# Light_Sensor.net
KiCad netlist of a schematic drawn in Altium Designer
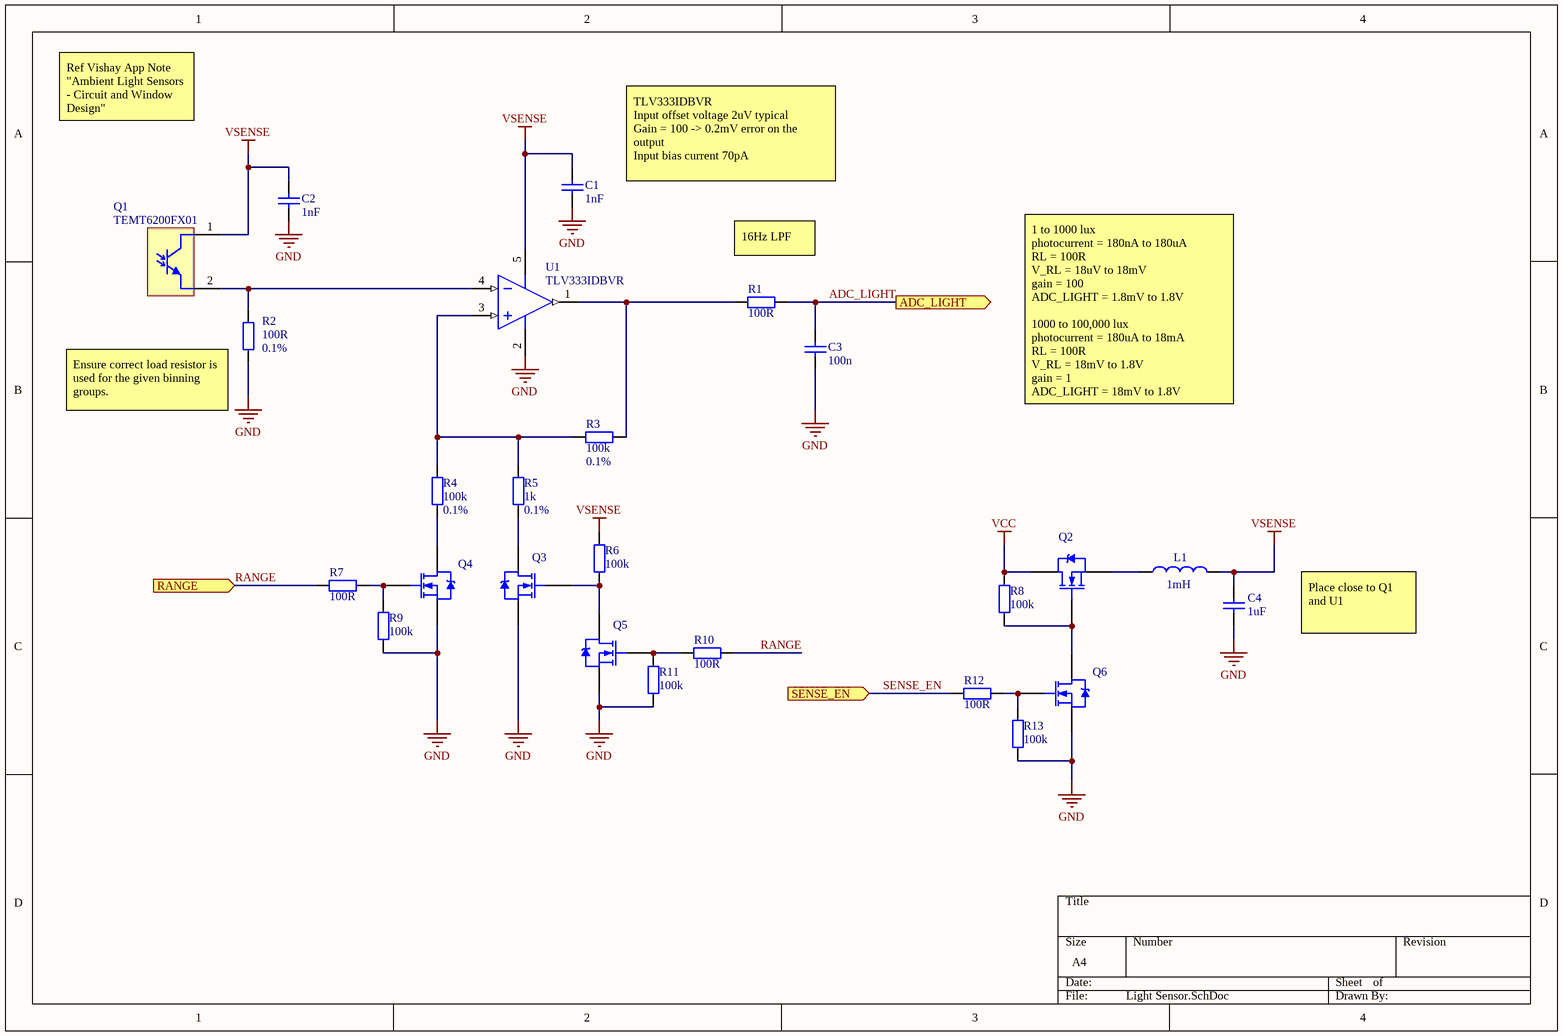
[diagram p0: Light Sensor.SchDoc]

(export (version "E")
  (design (tool "Eeschema 10.0.6"))
  (components
    (comp (ref "C1")
      (value "1nF")
      (footprint "C0603")
      (description "CAP")
      (fields
        (field (name "MANUFACTURER") "Yageo")
        (field (name "MANUFACTURER PART NUMBER") "CC0603KRX7R9BB102")
      )
      (libsource (lib "Light Sensor Node") (part "CAP"))
    )
    (comp (ref "C2")
      (value "1nF")
      (footprint "C0603")
      (description "CAP")
      (fields
        (field (name "MANUFACTURER") "Yageo")
        (field (name "MANUFACTURER PART NUMBER") "CC0603KRX7R9BB102")
      )
      (libsource (lib "Light Sensor Node") (part "CAP"))
    )
    (comp (ref "C3")
      (value "100n")
      (footprint "C0603")
      (description "CAP")
      (fields
        (field (name "MANUFACTURER") "Yageo")
        (field (name "MANUFACTURER PART NUMBER") "CC0603ZRY5V9BB104")
      )
      (libsource (lib "Light Sensor Node") (part "CAP"))
    )
    (comp (ref "C4")
      (value "~")
      (footprint "C0603")
      (description "CAP")
      (fields
        (field (name "MANUFACTURER") "Yageo")
        (field (name "MANUFACTURER PART NUMBER") "CC0603KRX7R9BB105")
        (field (name "CAPACITANCE") "1uF")
      )
      (libsource (lib "Light Sensor Node") (part "CAP"))
    )
    (comp (ref "L1")
      (value "IND")
      (footprint "TAIYOYUDEN_CB2518T102K")
      (fields
        (field (name "MANUFACTURER") "Taiyo Yuden")
        (field (name "MANUFACTURER PART NUMBER") "CB2518T102K")
        (field (name "INDUCTANCE") "1mH")
      )
      (libsource (lib "Light Sensor Node") (part "IND"))
    )
    (comp (ref "Q1")
      (value "TEMT6200FX01")
      (fields (field (name "MANUFACTURER") "Vishay"))
      (libsource (lib "Light Sensor Node") (part "VISHAY_TEMT6200FX01"))
    )
    (comp (ref "Q2")
      (value "2N7002ET1G")
      (footprint "ON_2N7002E")
      (fields (field (name "MANUFACTURER") "ON Semiconductor"))
      (libsource (lib "Light Sensor Node") (part "N-channel MOSFET"))
    )
    (comp (ref "Q3")
      (value "2N7002ET1G")
      (footprint "ON_2N7002E")
      (fields (field (name "MANUFACTURER") "ON Semiconductor"))
      (libsource (lib "Light Sensor Node") (part "N-channel MOSFET"))
    )
    (comp (ref "Q4")
      (value "2N7002ET1G")
      (footprint "ON_2N7002E")
      (fields (field (name "MANUFACTURER") "ON Semiconductor"))
      (libsource (lib "Light Sensor Node") (part "N-channel MOSFET"))
    )
    (comp (ref "Q5")
      (value "2N7002ET1G")
      (footprint "ON_2N7002E")
      (fields (field (name "MANUFACTURER") "ON Semiconductor"))
      (libsource (lib "Light Sensor Node") (part "N-channel MOSFET"))
    )
    (comp (ref "Q6")
      (value "2N7002ET1G")
      (footprint "ON_2N7002E")
      (fields (field (name "MANUFACTURER") "ON Semiconductor"))
      (libsource (lib "Light Sensor Node") (part "N-channel MOSFET"))
    )
    (comp (ref "R1")
      (value "100R")
      (footprint "R0603")
      (description "RES")
      (fields (field (name "TOLERANCE") "1%") (field (name "MANUFACTURER") "Yageo"))
      (libsource (lib "Light Sensor Node") (part "RES"))
    )
    (comp (ref "R2")
      (value "100R")
      (footprint "R0603")
      (description "RES")
      (fields
        (field (name "TOLERANCE") "0.1%")
        (field (name "MANUFACTURER") "Yageo")
        (field (name "MANUFACTURER PART NUMBER") "RT0603BRD07100RL")
      )
      (libsource (lib "") (part "RES_2"))
    )
    (comp (ref "R3")
      (value "100k")
      (footprint "R0603")
      (description "RES")
      (fields
        (field (name "TOLERANCE") "0.1%")
        (field (name "MANUFACTURER") "Yageo")
        (field (name "MANUFACTURER PART NUMBER") "RT0603BRD07100KL")
      )
      (libsource (lib "Light Sensor Node") (part "RES"))
    )
    (comp (ref "R4")
      (value "100k")
      (footprint "R0603")
      (description "RES")
      (fields
        (field (name "TOLERANCE") "0.1%")
        (field (name "MANUFACTURER") "Yageo")
        (field (name "MANUFACTURER PART NUMBER") "RT0603BRD07100KL")
      )
      (libsource (lib "") (part "RES_2"))
    )
    (comp (ref "R5")
      (value "1k")
      (footprint "R0603")
      (description "RES")
      (fields
        (field (name "TOLERANCE") "0.1%")
        (field (name "MANUFACTURER") "Yageo")
        (field (name "MANUFACTURER PART NUMBER") "RT0603BRD071KL")
      )
      (libsource (lib "") (part "RES_1"))
    )
    (comp (ref "R6")
      (value "100k")
      (footprint "R0603")
      (description "RES")
      (fields (field (name "TOLERANCE") "1%") (field (name "MANUFACTURER") "Yageo"))
      (libsource (lib "") (part "RES_1"))
    )
    (comp (ref "R7")
      (value "100R")
      (footprint "R0603")
      (description "RES")
      (fields (field (name "TOLERANCE") "1%") (field (name "MANUFACTURER") "Yageo"))
      (libsource (lib "Light Sensor Node") (part "RES"))
    )
    (comp (ref "R8")
      (value "100k")
      (footprint "R0603")
      (description "RES")
      (fields (field (name "TOLERANCE") "1%") (field (name "MANUFACTURER") "Yageo"))
      (libsource (lib "") (part "RES_1"))
    )
    (comp (ref "R9")
      (value "100k")
      (footprint "R0603")
      (description "RES")
      (fields (field (name "TOLERANCE") "1%") (field (name "MANUFACTURER") "Yageo"))
      (libsource (lib "") (part "RES_1"))
    )
    (comp (ref "R10")
      (value "100R")
      (footprint "R0603")
      (description "RES")
      (fields (field (name "TOLERANCE") "1%") (field (name "MANUFACTURER") "Yageo"))
      (libsource (lib "Light Sensor Node") (part "RES"))
    )
    (comp (ref "R11")
      (value "100k")
      (footprint "R0603")
      (description "RES")
      (fields (field (name "TOLERANCE") "1%") (field (name "MANUFACTURER") "Yageo"))
      (libsource (lib "") (part "RES_1"))
    )
    (comp (ref "R12")
      (value "100R")
      (footprint "R0603")
      (description "RES")
      (fields (field (name "TOLERANCE") "1%") (field (name "MANUFACTURER") "Yageo"))
      (libsource (lib "Light Sensor Node") (part "RES"))
    )
    (comp (ref "R13")
      (value "100k")
      (footprint "R0603")
      (description "RES")
      (fields (field (name "TOLERANCE") "1%") (field (name "MANUFACTURER") "Yageo"))
      (libsource (lib "") (part "RES_1"))
    )
    (comp (ref "U1")
      (value "TLV333IDBVR")
      (footprint "TI_TLV333IDBVR")
      (fields (field (name "MANUFACTURER") "Texas Instruments"))
      (libsource (lib "Light Sensor Node") (part "OPAMP"))
    )
  )
  (nets
    (net (code "1") (name "/ADC_LIGHT") (class "Default")
      (node (ref "C3") (pin "2") (pinfunction "2_2") (pintype "passive"))
      (node (ref "R1") (pin "2") (pinfunction "2_2") (pintype "passive"))
    )
    (net (code "2") (name "/RANGE") (class "Default")
      (node (ref "R10") (pin "2") (pinfunction "2_2") (pintype "passive"))
      (node (ref "R7") (pin "1") (pinfunction "1_1") (pintype "passive"))
    )
    (net (code "3") (name "/SENSE_EN") (class "Default")
      (node (ref "R12") (pin "1") (pinfunction "1_1") (pintype "passive"))
    )
    (net (code "4") (name "GND") (class "Default")
      (node (ref "C1") (pin "2") (pinfunction "2_2") (pintype "passive"))
      (node (ref "C2") (pin "2") (pinfunction "2_2") (pintype "passive"))
      (node (ref "C3") (pin "1") (pinfunction "1_1") (pintype "passive"))
      (node (ref "C4") (pin "1") (pinfunction "1_1") (pintype "passive"))
      (node (ref "Q3") (pin "2") (pinfunction "S_2") (pintype "passive"))
      (node (ref "Q4") (pin "2") (pinfunction "S_2") (pintype "passive"))
      (node (ref "Q5") (pin "2") (pinfunction "S_2") (pintype "passive"))
      (node (ref "Q6") (pin "2") (pinfunction "S_2") (pintype "passive"))
      (node (ref "R11") (pin "2") (pinfunction "2_2") (pintype "passive"))
      (node (ref "R13") (pin "2") (pinfunction "2_2") (pintype "passive"))
      (node (ref "R2") (pin "1") (pinfunction "1_1") (pintype "passive"))
      (node (ref "R9") (pin "2") (pinfunction "2_2") (pintype "passive"))
      (node (ref "U1") (pin "2") (pinfunction "V-_2") (pintype "power_in"))
    )
    (net (code "5") (name "Net-(Q1-E)") (class "Default")
      (node (ref "Q1") (pin "2") (pinfunction "E_2") (pintype "passive"))
      (node (ref "R2") (pin "2") (pinfunction "2_2") (pintype "passive"))
      (node (ref "U1") (pin "4") (pinfunction "IN_A-_4") (pintype "input"))
    )
    (net (code "6") (name "Net-(Q2-G)") (class "Default")
      (node (ref "Q2") (pin "1") (pinfunction "G_1") (pintype "passive"))
      (node (ref "Q6") (pin "3") (pinfunction "D_3") (pintype "passive"))
      (node (ref "R8") (pin "2") (pinfunction "2_2") (pintype "passive"))
    )
    (net (code "7") (name "Net-(Q2-S)") (class "Default")
      (node (ref "L1") (pin "2") (pinfunction "2_2") (pintype "passive"))
      (node (ref "Q2") (pin "2") (pinfunction "S_2") (pintype "passive"))
    )
    (net (code "8") (name "Net-(Q3-D)") (class "Default")
      (node (ref "Q3") (pin "3") (pinfunction "D_3") (pintype "passive"))
      (node (ref "R5") (pin "2") (pinfunction "2_2") (pintype "passive"))
    )
    (net (code "9") (name "Net-(Q3-G)") (class "Default")
      (node (ref "Q3") (pin "1") (pinfunction "G_1") (pintype "passive"))
      (node (ref "Q5") (pin "3") (pinfunction "D_3") (pintype "passive"))
      (node (ref "R6") (pin "2") (pinfunction "2_2") (pintype "passive"))
    )
    (net (code "10") (name "Net-(Q4-D)") (class "Default")
      (node (ref "Q4") (pin "3") (pinfunction "D_3") (pintype "passive"))
      (node (ref "R4") (pin "1") (pinfunction "1_1") (pintype "passive"))
    )
    (net (code "11") (name "Net-(Q4-G)") (class "Default")
      (node (ref "Q4") (pin "1") (pinfunction "G_1") (pintype "passive"))
      (node (ref "R7") (pin "2") (pinfunction "2_2") (pintype "passive"))
      (node (ref "R9") (pin "1") (pinfunction "1_1") (pintype "passive"))
    )
    (net (code "12") (name "Net-(Q5-G)") (class "Default")
      (node (ref "Q5") (pin "1") (pinfunction "G_1") (pintype "passive"))
      (node (ref "R10") (pin "1") (pinfunction "1_1") (pintype "passive"))
      (node (ref "R11") (pin "1") (pinfunction "1_1") (pintype "passive"))
    )
    (net (code "13") (name "Net-(Q6-G)") (class "Default")
      (node (ref "Q6") (pin "1") (pinfunction "G_1") (pintype "passive"))
      (node (ref "R12") (pin "2") (pinfunction "2_2") (pintype "passive"))
      (node (ref "R13") (pin "1") (pinfunction "1_1") (pintype "passive"))
    )
    (net (code "14") (name "Net-(U1-IN_A+)") (class "Default")
      (node (ref "R3") (pin "1") (pinfunction "1_1") (pintype "passive"))
      (node (ref "R4") (pin "2") (pinfunction "2_2") (pintype "passive"))
      (node (ref "R5") (pin "1") (pinfunction "1_1") (pintype "passive"))
      (node (ref "U1") (pin "3") (pinfunction "IN_A+_3") (pintype "input"))
    )
    (net (code "15") (name "Net-(U1-OUT_A)") (class "Default")
      (node (ref "R1") (pin "1") (pinfunction "1_1") (pintype "passive"))
      (node (ref "R3") (pin "2") (pinfunction "2_2") (pintype "passive"))
      (node (ref "U1") (pin "1") (pinfunction "OUT_A_1") (pintype "output"))
    )
    (net (code "16") (name "VCC") (class "Default")
      (node (ref "Q2") (pin "3") (pinfunction "D_3") (pintype "passive"))
      (node (ref "R8") (pin "1") (pinfunction "1_1") (pintype "passive"))
    )
    (net (code "17") (name "VSENSE") (class "Default")
      (node (ref "C1") (pin "1") (pinfunction "1_1") (pintype "passive"))
      (node (ref "C2") (pin "1") (pinfunction "1_1") (pintype "passive"))
      (node (ref "C4") (pin "2") (pinfunction "2_2") (pintype "passive"))
      (node (ref "L1") (pin "1") (pinfunction "1_1") (pintype "passive"))
      (node (ref "Q1") (pin "1") (pinfunction "C_1") (pintype "passive"))
      (node (ref "R6") (pin "1") (pinfunction "1_1") (pintype "passive"))
      (node (ref "U1") (pin "5") (pinfunction "V+_5") (pintype "power_in"))
    )
  )
)
